# mclon_nano_0_1.net
KiCad netlist of a schematic drawn in EAGLE
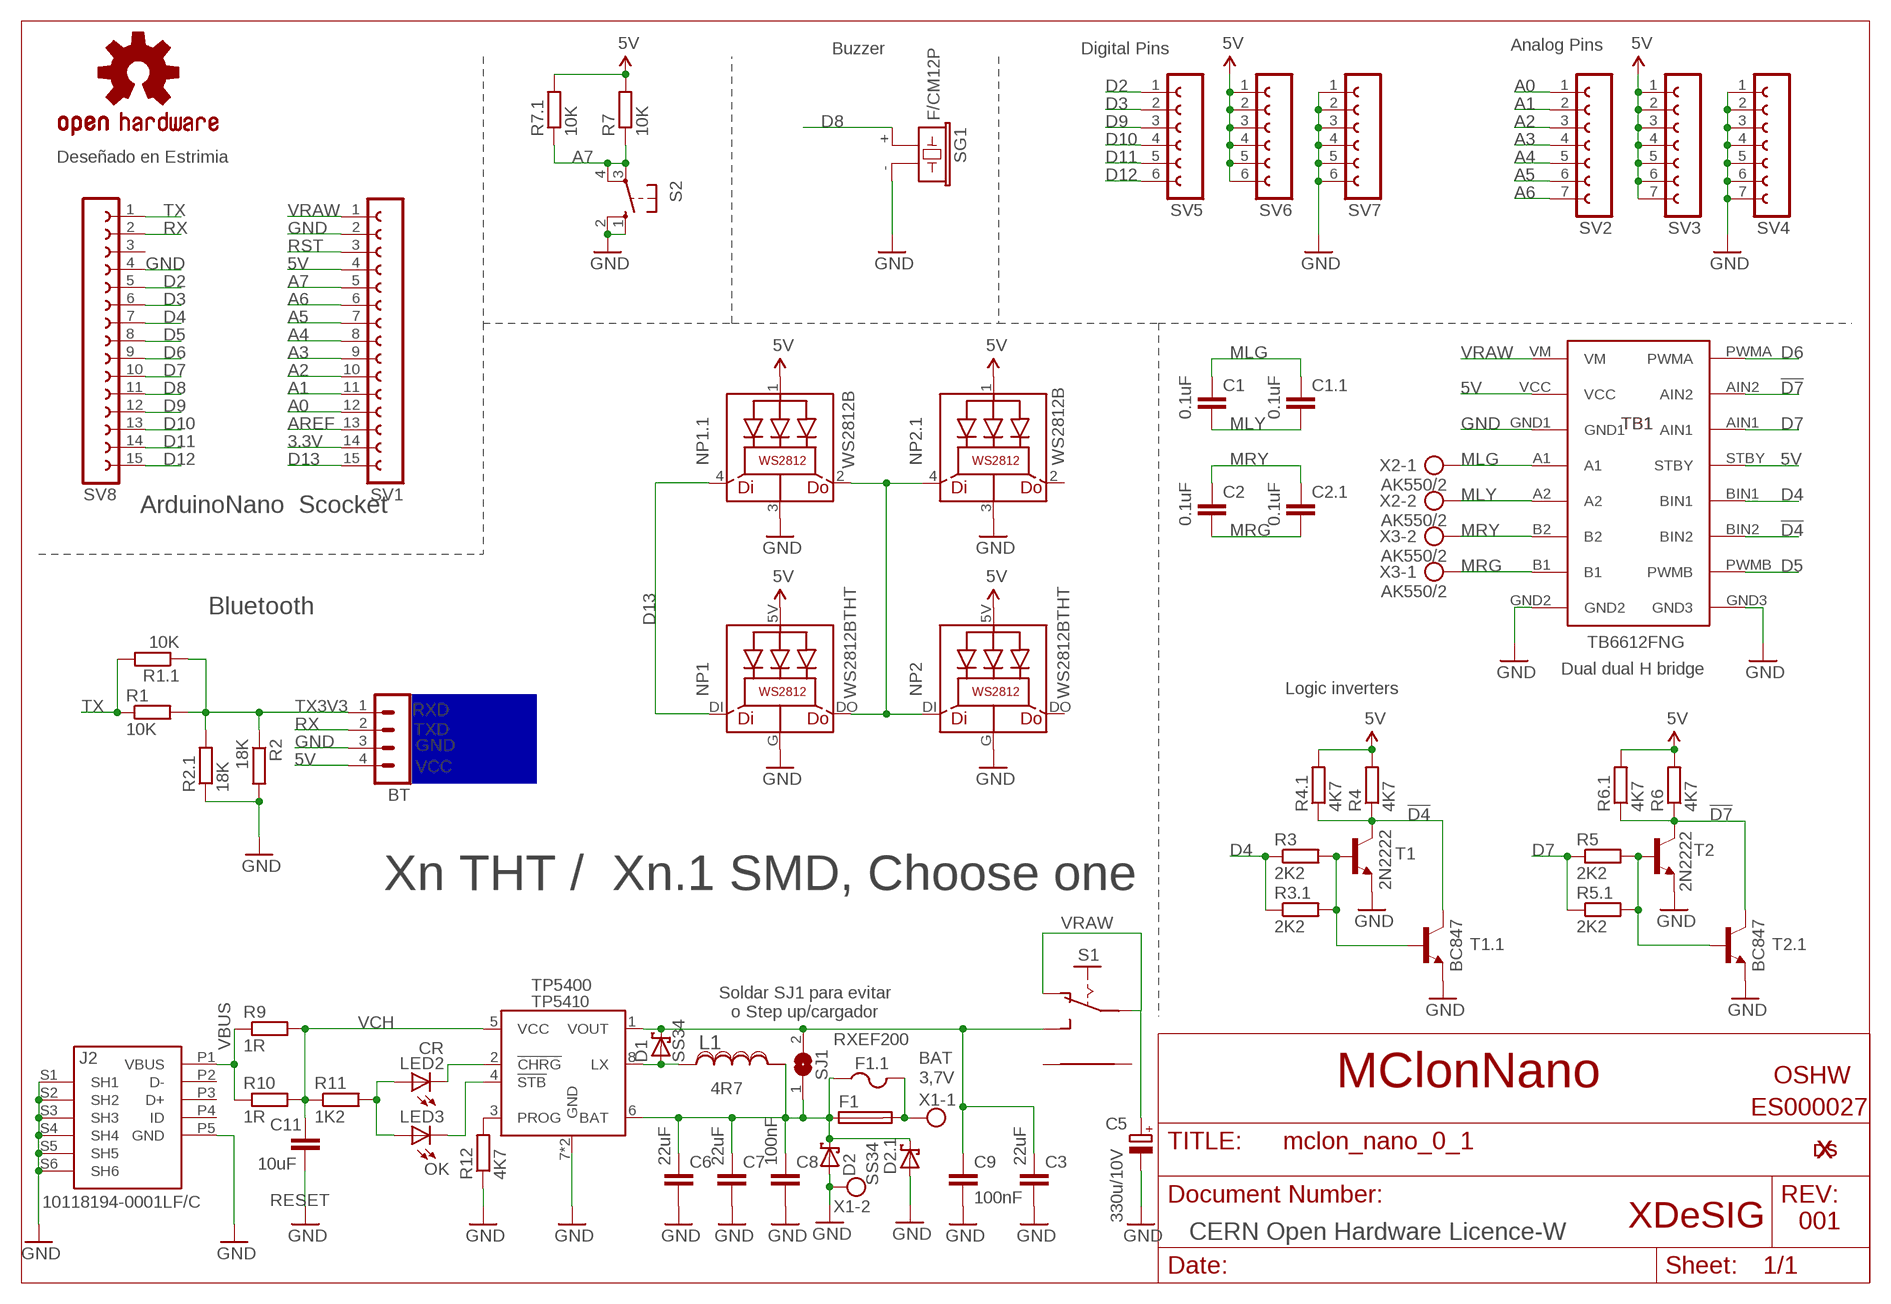
[diagram p0: schematic, sheet 1]

(export (version "E")
  (design (tool "Eeschema 10.0.6"))
  (components
    (comp (ref "BT")
      (value "MA04-1")
      (footprint "eagle-import:MA04-1")
      (libsource (lib "eagle-import") (part "MA04-1"))
    )
    (comp (ref "C1")
      (value "0.1uF")
      (footprint "eagle-import:C050-024X044")
      (libsource (lib "eagle-import") (part "C-EU050-024X044"))
    )
    (comp (ref "C1.1")
      (value "0.1uF")
      (footprint "eagle-import:C1206")
      (libsource (lib "eagle-import") (part "C-EUC1206"))
    )
    (comp (ref "C2")
      (value "0.1uF")
      (footprint "eagle-import:C050-024X044")
      (libsource (lib "eagle-import") (part "C-EU050-024X044"))
    )
    (comp (ref "C2.1")
      (value "0.1uF")
      (footprint "eagle-import:C1206")
      (libsource (lib "eagle-import") (part "C-EUC1206"))
    )
    (comp (ref "C3")
      (value "22uF")
      (footprint "eagle-import:C1206")
      (libsource (lib "eagle-import") (part "C-EUC1206"))
    )
    (comp (ref "C5")
      (value "330u/10V")
      (footprint "eagle-import:E2,5-6")
      (libsource (lib "eagle-import") (part "CPOL-EUE2.5-6"))
    )
    (comp (ref "C6")
      (value "22uF")
      (footprint "eagle-import:C1206")
      (libsource (lib "eagle-import") (part "C-EUC1206"))
    )
    (comp (ref "C7")
      (value "22uF")
      (footprint "eagle-import:C1206")
      (libsource (lib "eagle-import") (part "C-EUC1206"))
    )
    (comp (ref "C8")
      (value "100nF")
      (footprint "eagle-import:C1206")
      (libsource (lib "eagle-import") (part "C-EUC1206"))
    )
    (comp (ref "C9")
      (value "100nF")
      (footprint "eagle-import:C1206")
      (libsource (lib "eagle-import") (part "C-EUC1206"))
    )
    (comp (ref "C11")
      (value "10uF")
      (footprint "eagle-import:C1206")
      (libsource (lib "eagle-import") (part "C-EUC1206"))
    )
    (comp (ref "D1")
      (value "SS34")
      (footprint "eagle-import:DIODE_SMA")
      (libsource (lib "eagle-import") (part "DIODE_SCHOTTKY-DIODESMA"))
    )
    (comp (ref "D2")
      (value "SS34")
      (footprint "eagle-import:DIODE_SMA")
      (libsource (lib "eagle-import") (part "DIODE_SCHOTTKY-DIODESMA"))
    )
    (comp (ref "D2.1")
      (value "SCHOTTKY-DIODEDO35-7")
      (footprint "eagle-import:DO35-7")
      (libsource (lib "eagle-import") (part "SCHOTTKY-DIODEDO35-7"))
    )
    (comp (ref "F1")
      (value "RXEF200")
      (footprint "eagle-import:TE5")
      (libsource (lib "eagle-import") (part "FUSETE5"))
    )
    (comp (ref "F1.1")
      (value "MF-NSMF200")
      (footprint "eagle-import:1812")
      (libsource (lib "eagle-import") (part "PTCFUSE-1812"))
    )
    (comp (ref "J2")
      (value "10118194-0001LF/C")
      (footprint "eagle-import:SMARTPRJ_CON2_USB_MICRO_B_AT")
      (libsource (lib "eagle-import") (part "SMARTPRJ_MYCON2_USB-MINI-B"))
    )
    (comp (ref "L1")
      (value "4R7")
      (footprint "eagle-import:SRN6045")
      (fields (field (name "MF") "Bourns") (field (name "MP") "SRN6045-330M"))
      (libsource (lib "eagle-import") (part "SRN6045-330M6045"))
    )
    (comp (ref "LED2")
      (value "CR")
      (footprint "eagle-import:CHIPLED_0805")
      (libsource (lib "eagle-import") (part "LEDCHIPLED_0805"))
    )
    (comp (ref "LED3")
      (value "OK")
      (footprint "eagle-import:CHIPLED_0805")
      (libsource (lib "eagle-import") (part "LEDCHIPLED_0805"))
    )
    (comp (ref "LOGO4")
      (value "OSHW-LOGOS")
      (footprint "eagle-import:OSHW-LOGO-S")
      (libsource (lib "eagle-import") (part "OSHW-LOGOS"))
    )
    (comp (ref "NP1")
      (value "WS2812BTHT")
      (footprint "eagle-import:NEOPIXEL5MM")
      (libsource (lib "eagle-import") (part "WS2812BTHT"))
    )
    (comp (ref "NP1.1")
      (value "WS2812B")
      (footprint "eagle-import:5050-4")
      (libsource (lib "eagle-import") (part "WS2812B"))
    )
    (comp (ref "NP2")
      (value "WS2812BTHT")
      (footprint "eagle-import:NEOPIXEL5MM")
      (libsource (lib "eagle-import") (part "WS2812BTHT"))
    )
    (comp (ref "NP2.1")
      (value "WS2812B")
      (footprint "eagle-import:5050-4")
      (libsource (lib "eagle-import") (part "WS2812B"))
    )
    (comp (ref "R1")
      (value "10K")
      (footprint "eagle-import:0204_7")
      (libsource (lib "eagle-import") (part "R-EU_0204/7"))
    )
    (comp (ref "R1.1")
      (value "10K")
      (footprint "eagle-import:R1206")
      (libsource (lib "eagle-import") (part "R-EU_R1206"))
    )
    (comp (ref "R2")
      (value "18K")
      (footprint "eagle-import:0204_7")
      (libsource (lib "eagle-import") (part "R-EU_0204/7"))
    )
    (comp (ref "R2.1")
      (value "18K")
      (footprint "eagle-import:R1206")
      (libsource (lib "eagle-import") (part "R-EU_R1206"))
    )
    (comp (ref "R3")
      (value "2K2")
      (footprint "eagle-import:0204_7")
      (libsource (lib "eagle-import") (part "R-EU_0204/7"))
    )
    (comp (ref "R3.1")
      (value "2K2")
      (footprint "eagle-import:R1206")
      (libsource (lib "eagle-import") (part "R-EU_R1206"))
    )
    (comp (ref "R4")
      (value "4K7")
      (footprint "eagle-import:0204_7")
      (libsource (lib "eagle-import") (part "R-EU_0204/7"))
    )
    (comp (ref "R4.1")
      (value "4K7")
      (footprint "eagle-import:R1206")
      (libsource (lib "eagle-import") (part "R-EU_R1206"))
    )
    (comp (ref "R5")
      (value "2K2")
      (footprint "eagle-import:0204_7")
      (libsource (lib "eagle-import") (part "R-EU_0204/7"))
    )
    (comp (ref "R5.1")
      (value "2K2")
      (footprint "eagle-import:R1206")
      (libsource (lib "eagle-import") (part "R-EU_R1206"))
    )
    (comp (ref "R6")
      (value "4K7")
      (footprint "eagle-import:0204_7")
      (libsource (lib "eagle-import") (part "R-EU_0204/7"))
    )
    (comp (ref "R6.1")
      (value "4K7")
      (footprint "eagle-import:R1206")
      (libsource (lib "eagle-import") (part "R-EU_R1206"))
    )
    (comp (ref "R7")
      (value "10K")
      (footprint "eagle-import:0204_7")
      (libsource (lib "eagle-import") (part "R-EU_0204/7"))
    )
    (comp (ref "R7.1")
      (value "10K")
      (footprint "eagle-import:R1206")
      (libsource (lib "eagle-import") (part "R-EU_R1206"))
    )
    (comp (ref "R9")
      (value "1R")
      (footprint "eagle-import:M1206")
      (libsource (lib "eagle-import") (part "R-EU_M1206"))
    )
    (comp (ref "R10")
      (value "1R")
      (footprint "eagle-import:M1206")
      (libsource (lib "eagle-import") (part "R-EU_M1206"))
    )
    (comp (ref "R11")
      (value "1K2")
      (footprint "eagle-import:R1206")
      (libsource (lib "eagle-import") (part "R-EU_R1206"))
    )
    (comp (ref "R12")
      (value "4K7")
      (footprint "eagle-import:R1206")
      (libsource (lib "eagle-import") (part "R-EU_R1206"))
    )
    (comp (ref "S1")
      (value "ESCORNA_SK12F14D")
      (footprint "eagle-import:ESCORNA_SK-12D07")
      (libsource (lib "eagle-import") (part "ESCORNA_SK12F14D"))
    )
    (comp (ref "S2")
      (value "10-XX")
      (footprint "eagle-import:B3F-10XX")
      (fields (field (name "MPN") "B3F-1000"))
      (libsource (lib "eagle-import") (part "10-XX"))
    )
    (comp (ref "SG1")
      (value "F/CM12P")
      (footprint "eagle-import:F_CM12P")
      (libsource (lib "eagle-import") (part "F/CM12P"))
    )
    (comp (ref "SJ1")
      (value "JUMPER_SJW")
      (footprint "eagle-import:JUMPER_SJW")
      (libsource (lib "eagle-import") (part "JUMPER_SJW"))
    )
    (comp (ref "SV1")
      (value "CON-LSTA_FE15-1")
      (footprint "eagle-import:CON-LSTA_FE15")
      (libsource (lib "eagle-import") (part "CON-LSTA_FE15-1"))
    )
    (comp (ref "SV2")
      (value "FE07-1")
      (footprint "eagle-import:FE07")
      (libsource (lib "eagle-import") (part "FE07-1"))
    )
    (comp (ref "SV3")
      (value "FE07-1")
      (footprint "eagle-import:FE07")
      (libsource (lib "eagle-import") (part "FE07-1"))
    )
    (comp (ref "SV4")
      (value "FE07-1")
      (footprint "eagle-import:FE07")
      (libsource (lib "eagle-import") (part "FE07-1"))
    )
    (comp (ref "SV5")
      (value "FE06-1")
      (footprint "eagle-import:FE06")
      (libsource (lib "eagle-import") (part "FE06-1"))
    )
    (comp (ref "SV6")
      (value "FE06-1")
      (footprint "eagle-import:FE06")
      (libsource (lib "eagle-import") (part "FE06-1"))
    )
    (comp (ref "SV7")
      (value "FE06-1")
      (footprint "eagle-import:FE06")
      (libsource (lib "eagle-import") (part "FE06-1"))
    )
    (comp (ref "SV8")
      (value "CON-LSTA_FE15-1")
      (footprint "eagle-import:CON-LSTA_FE15")
      (libsource (lib "eagle-import") (part "CON-LSTA_FE15-1"))
    )
    (comp (ref "T1")
      (value "2N2222")
      (footprint "eagle-import:TO92-EBC-OVAL")
      (libsource (lib "eagle-import") (part "2N2222"))
    )
    (comp (ref "T1.1")
      (value "BC847")
      (footprint "eagle-import:SOT23")
      (libsource (lib "eagle-import") (part "BC847"))
    )
    (comp (ref "T2")
      (value "2N2222")
      (footprint "eagle-import:TO92-EBC-OVAL")
      (libsource (lib "eagle-import") (part "2N2222"))
    )
    (comp (ref "T2.1")
      (value "BC847")
      (footprint "eagle-import:SOT23")
      (libsource (lib "eagle-import") (part "BC847"))
    )
    (comp (ref "TB1")
      (value "TB6612FNG")
      (footprint "eagle-import:TB6612FNG")
      (libsource (lib "eagle-import") (part "TB6612FNG"))
    )
    (comp (ref "U$7")
      (value "OSHW")
      (footprint "eagle-import:OSHW")
      (libsource (lib "eagle-import") (part "OSHW"))
    )
    (comp (ref "U$8")
      (value "XDESIG5MM")
      (footprint "eagle-import:XDESIG_CU")
      (libsource (lib "eagle-import") (part "XDESIG5MM"))
    )
    (comp (ref "U$18")
      (value "XDESIG21")
      (footprint "eagle-import:XDESIG")
      (libsource (lib "eagle-import") (part "XDESIG21"))
    )
    (comp (ref "U$19")
      (value "XDESIG5MM")
      (footprint "eagle-import:XDESIG_CU")
      (libsource (lib "eagle-import") (part "XDESIG5MM"))
    )
    (comp (ref "U1")
      (value "TP5400")
      (footprint "eagle-import:ESOP8")
      (libsource (lib "eagle-import") (part "TP5400"))
    )
    (comp (ref "X1")
      (value "AK550/2")
      (footprint "eagle-import:AK550_2")
      (libsource (lib "eagle-import") (part "AK550/2"))
    )
    (comp (ref "X2")
      (value "AK550/2")
      (footprint "eagle-import:AK550_2")
      (libsource (lib "eagle-import") (part "AK550/2"))
    )
    (comp (ref "X3")
      (value "AK550/2")
      (footprint "eagle-import:AK550_2")
      (libsource (lib "eagle-import") (part "AK550/2"))
    )
  )
  (nets
    (net (code "1") (name "/3.3V") (class "Default")
      (node (ref "SV1") (pin "14") (pinfunction "14_14") (pintype "passive"))
    )
    (net (code "2") (name "/A0") (class "Default")
      (node (ref "SV1") (pin "12") (pinfunction "12_12") (pintype "passive"))
      (node (ref "SV2") (pin "1") (pinfunction "1_1") (pintype "passive"))
    )
    (net (code "3") (name "/A1") (class "Default")
      (node (ref "SV1") (pin "11") (pinfunction "11_11") (pintype "passive"))
      (node (ref "SV2") (pin "2") (pinfunction "2_2") (pintype "passive"))
    )
    (net (code "4") (name "/A2") (class "Default")
      (node (ref "SV1") (pin "10") (pinfunction "10_10") (pintype "passive"))
      (node (ref "SV2") (pin "3") (pinfunction "3_3") (pintype "passive"))
    )
    (net (code "5") (name "/A3") (class "Default")
      (node (ref "SV1") (pin "9") (pinfunction "9_9") (pintype "passive"))
      (node (ref "SV2") (pin "4") (pinfunction "4_4") (pintype "passive"))
    )
    (net (code "6") (name "/A4") (class "Default")
      (node (ref "SV1") (pin "8") (pinfunction "8_8") (pintype "passive"))
      (node (ref "SV2") (pin "5") (pinfunction "5_5") (pintype "passive"))
    )
    (net (code "7") (name "/A5") (class "Default")
      (node (ref "SV1") (pin "7") (pinfunction "7_7") (pintype "passive"))
      (node (ref "SV2") (pin "6") (pinfunction "6_6") (pintype "passive"))
    )
    (net (code "8") (name "/A6") (class "Default")
      (node (ref "SV1") (pin "6") (pinfunction "6_6") (pintype "passive"))
      (node (ref "SV2") (pin "7") (pinfunction "7_7") (pintype "passive"))
    )
    (net (code "9") (name "/A7") (class "Default")
      (node (ref "R7") (pin "1") (pinfunction "1_1") (pintype "passive"))
      (node (ref "R7.1") (pin "1") (pinfunction "1_1") (pintype "passive"))
      (node (ref "S2") (pin "3") (pinfunction "P_3") (pintype "passive"))
      (node (ref "S2") (pin "4") (pinfunction "P1_4") (pintype "passive"))
      (node (ref "SV1") (pin "5") (pinfunction "5_5") (pintype "passive"))
    )
    (net (code "10") (name "/AREF") (class "Default")
      (node (ref "SV1") (pin "13") (pinfunction "13_13") (pintype "passive"))
    )
    (net (code "11") (name "/BAT") (class "Default")
      (node (ref "C6") (pin "1") (pinfunction "1_1") (pintype "passive"))
      (node (ref "C7") (pin "1") (pinfunction "1_1") (pintype "passive"))
      (node (ref "C8") (pin "1") (pinfunction "1_1") (pintype "passive"))
      (node (ref "D2") (pin "C") (pinfunction "C_C") (pintype "passive"))
      (node (ref "D2.1") (pin "C") (pinfunction "C_C") (pintype "passive"))
      (node (ref "F1") (pin "1") (pinfunction "1_1") (pintype "passive"))
      (node (ref "F1.1") (pin "1") (pinfunction "1_1") (pintype "passive"))
      (node (ref "L1") (pin "1") (pinfunction "1_1") (pintype "passive"))
      (node (ref "SJ1") (pin "1") (pinfunction "1_1") (pintype "passive"))
      (node (ref "U1") (pin "6") (pinfunction "BAT_6") (pintype "bidirectional"))
    )
    (net (code "12") (name "/D2") (class "Default")
      (node (ref "SV5") (pin "1") (pinfunction "1_1") (pintype "passive"))
      (node (ref "SV8") (pin "5") (pinfunction "5_5") (pintype "passive"))
    )
    (net (code "13") (name "/D3") (class "Default")
      (node (ref "SV5") (pin "2") (pinfunction "2_2") (pintype "passive"))
      (node (ref "SV8") (pin "6") (pinfunction "6_6") (pintype "passive"))
    )
    (net (code "14") (name "/D4") (class "Default")
      (node (ref "R3") (pin "1") (pinfunction "1_1") (pintype "passive"))
      (node (ref "R3.1") (pin "1") (pinfunction "1_1") (pintype "passive"))
      (node (ref "SV8") (pin "7") (pinfunction "7_7") (pintype "passive"))
      (node (ref "TB1") (pin "BIN1") (pinfunction "BIN1_BIN1") (pintype "bidirectional"))
    )
    (net (code "15") (name "/D5") (class "Default")
      (node (ref "SV8") (pin "8") (pinfunction "8_8") (pintype "passive"))
      (node (ref "TB1") (pin "PWMB") (pinfunction "PWMB_PWMB") (pintype "bidirectional"))
    )
    (net (code "16") (name "/D6") (class "Default")
      (node (ref "SV8") (pin "9") (pinfunction "9_9") (pintype "passive"))
      (node (ref "TB1") (pin "PWMA") (pinfunction "PWMA_PWMA") (pintype "bidirectional"))
    )
    (net (code "17") (name "/D7") (class "Default")
      (node (ref "R5") (pin "1") (pinfunction "1_1") (pintype "passive"))
      (node (ref "R5.1") (pin "1") (pinfunction "1_1") (pintype "passive"))
      (node (ref "SV8") (pin "10") (pinfunction "10_10") (pintype "passive"))
      (node (ref "TB1") (pin "AIN1") (pinfunction "AIN1_AIN1") (pintype "bidirectional"))
    )
    (net (code "18") (name "/D8") (class "Default")
      (node (ref "SG1") (pin "+") (pinfunction "1_+") (pintype "passive"))
      (node (ref "SV8") (pin "11") (pinfunction "11_11") (pintype "passive"))
    )
    (net (code "19") (name "/D9") (class "Default")
      (node (ref "SV5") (pin "3") (pinfunction "3_3") (pintype "passive"))
      (node (ref "SV8") (pin "12") (pinfunction "12_12") (pintype "passive"))
    )
    (net (code "20") (name "/D10") (class "Default")
      (node (ref "SV5") (pin "4") (pinfunction "4_4") (pintype "passive"))
      (node (ref "SV8") (pin "13") (pinfunction "13_13") (pintype "passive"))
    )
    (net (code "21") (name "/D11") (class "Default")
      (node (ref "SV5") (pin "5") (pinfunction "5_5") (pintype "passive"))
      (node (ref "SV8") (pin "14") (pinfunction "14_14") (pintype "passive"))
    )
    (net (code "22") (name "/D12") (class "Default")
      (node (ref "SV5") (pin "6") (pinfunction "6_6") (pintype "passive"))
      (node (ref "SV8") (pin "15") (pinfunction "15_15") (pintype "passive"))
    )
    (net (code "23") (name "/D13") (class "Default")
      (node (ref "NP1") (pin "DI") (pinfunction "DI_DI") (pintype "input"))
      (node (ref "NP1.1") (pin "4") (pinfunction "DI_4") (pintype "input"))
      (node (ref "SV1") (pin "15") (pinfunction "15_15") (pintype "passive"))
    )
    (net (code "24") (name "/MLG") (class "Default")
      (node (ref "C1") (pin "1") (pinfunction "1_1") (pintype "passive"))
      (node (ref "C1.1") (pin "1") (pinfunction "1_1") (pintype "passive"))
      (node (ref "TB1") (pin "A1") (pinfunction "A1_A1") (pintype "bidirectional"))
      (node (ref "X2") (pin "1") (pinfunction "KL_1") (pintype "passive"))
    )
    (net (code "25") (name "/MLY") (class "Default")
      (node (ref "C1") (pin "2") (pinfunction "2_2") (pintype "passive"))
      (node (ref "C1.1") (pin "2") (pinfunction "2_2") (pintype "passive"))
      (node (ref "TB1") (pin "A2") (pinfunction "A2_A2") (pintype "bidirectional"))
      (node (ref "X2") (pin "2") (pinfunction "KL_2") (pintype "passive"))
    )
    (net (code "26") (name "/MRG") (class "Default")
      (node (ref "C2") (pin "2") (pinfunction "2_2") (pintype "passive"))
      (node (ref "C2.1") (pin "2") (pinfunction "2_2") (pintype "passive"))
      (node (ref "TB1") (pin "B1") (pinfunction "B1_B1") (pintype "bidirectional"))
      (node (ref "X3") (pin "1") (pinfunction "KL_1") (pintype "passive"))
    )
    (net (code "27") (name "/MRY") (class "Default")
      (node (ref "C2") (pin "1") (pinfunction "1_1") (pintype "passive"))
      (node (ref "C2.1") (pin "1") (pinfunction "1_1") (pintype "passive"))
      (node (ref "TB1") (pin "B2") (pinfunction "B2_B2") (pintype "bidirectional"))
      (node (ref "X3") (pin "2") (pinfunction "KL_2") (pintype "passive"))
    )
    (net (code "29") (name "/RST") (class "Default")
      (node (ref "SV1") (pin "3") (pinfunction "3_3") (pintype "passive"))
    )
    (net (code "30") (name "/RX") (class "Default")
      (node (ref "BT") (pin "2") (pinfunction "2_2") (pintype "passive"))
      (node (ref "SV8") (pin "2") (pinfunction "2_2") (pintype "passive"))
    )
    (net (code "31") (name "/TX") (class "Default")
      (node (ref "R1") (pin "1") (pinfunction "1_1") (pintype "passive"))
      (node (ref "R1.1") (pin "2") (pinfunction "2_2") (pintype "passive"))
      (node (ref "SV8") (pin "1") (pinfunction "1_1") (pintype "passive"))
    )
    (net (code "32") (name "/TX3V3") (class "Default")
      (node (ref "BT") (pin "1") (pinfunction "1_1") (pintype "passive"))
      (node (ref "R1") (pin "2") (pinfunction "2_2") (pintype "passive"))
      (node (ref "R1.1") (pin "1") (pinfunction "1_1") (pintype "passive"))
      (node (ref "R2") (pin "1") (pinfunction "1_1") (pintype "passive"))
      (node (ref "R2.1") (pin "2") (pinfunction "2_2") (pintype "passive"))
    )
    (net (code "33") (name "/VBUS") (class "Default")
      (node (ref "J2") (pin "P1") (pinfunction "VBUS_P1") (pintype "power_in"))
      (node (ref "R10") (pin "1") (pinfunction "1_1") (pintype "passive"))
      (node (ref "R9") (pin "1") (pinfunction "1_1") (pintype "passive"))
    )
    (net (code "34") (name "/VCH") (class "Default")
      (node (ref "C11") (pin "1") (pinfunction "1_1") (pintype "passive"))
      (node (ref "R10") (pin "2") (pinfunction "2_2") (pintype "passive"))
      (node (ref "R11") (pin "1") (pinfunction "1_1") (pintype "passive"))
      (node (ref "R9") (pin "2") (pinfunction "2_2") (pintype "passive"))
      (node (ref "U1") (pin "5") (pinfunction "VCC_5") (pintype "power_in"))
    )
    (net (code "35") (name "/VRAW") (class "Default")
      (node (ref "C5") (pin "+") (pinfunction "+_+") (pintype "passive"))
      (node (ref "S1") (pin "P$1") (pinfunction "P_P$1") (pintype "passive"))
      (node (ref "S1") (pin "P$2") (pinfunction "O_P$2") (pintype "passive"))
      (node (ref "SV1") (pin "1") (pinfunction "1_1") (pintype "passive"))
      (node (ref "TB1") (pin "VM") (pinfunction "VM_VM") (pintype "bidirectional"))
    )
    (net (code "36") (name "/~{D4}") (class "Default")
      (node (ref "R4") (pin "1") (pinfunction "1_1") (pintype "passive"))
      (node (ref "R4.1") (pin "1") (pinfunction "1_1") (pintype "passive"))
      (node (ref "T1") (pin "C") (pinfunction "C_C") (pintype "passive"))
      (node (ref "T1.1") (pin "3") (pinfunction "C_3") (pintype "passive"))
      (node (ref "TB1") (pin "BIN2") (pinfunction "BIN2_BIN2") (pintype "bidirectional"))
    )
    (net (code "37") (name "/~{D7}") (class "Default")
      (node (ref "R6") (pin "1") (pinfunction "1_1") (pintype "passive"))
      (node (ref "R6.1") (pin "1") (pinfunction "1_1") (pintype "passive"))
      (node (ref "T2") (pin "C") (pinfunction "C_C") (pintype "passive"))
      (node (ref "T2.1") (pin "3") (pinfunction "C_3") (pintype "passive"))
      (node (ref "TB1") (pin "AIN2") (pinfunction "AIN2_AIN2") (pintype "bidirectional"))
    )
    (net (code "38") (name "5V") (class "Default")
      (node (ref "BT") (pin "4") (pinfunction "4_4") (pintype "passive"))
      (node (ref "NP1") (pin "5V") (pinfunction "LEDVDD_5V") (pintype "power_in"))
      (node (ref "NP1.1") (pin "1") (pinfunction "LEDVDD_1") (pintype "power_in"))
      (node (ref "NP2") (pin "5V") (pinfunction "LEDVDD_5V") (pintype "power_in"))
      (node (ref "NP2.1") (pin "1") (pinfunction "LEDVDD_1") (pintype "power_in"))
      (node (ref "R4") (pin "2") (pinfunction "2_2") (pintype "passive"))
      (node (ref "R4.1") (pin "2") (pinfunction "2_2") (pintype "passive"))
      (node (ref "R6") (pin "2") (pinfunction "2_2") (pintype "passive"))
      (node (ref "R6.1") (pin "2") (pinfunction "2_2") (pintype "passive"))
      (node (ref "R7") (pin "2") (pinfunction "2_2") (pintype "passive"))
      (node (ref "R7.1") (pin "2") (pinfunction "2_2") (pintype "passive"))
      (node (ref "SV1") (pin "4") (pinfunction "4_4") (pintype "passive"))
      (node (ref "SV3") (pin "1") (pinfunction "1_1") (pintype "passive"))
      (node (ref "SV3") (pin "2") (pinfunction "2_2") (pintype "passive"))
      (node (ref "SV3") (pin "3") (pinfunction "3_3") (pintype "passive"))
      (node (ref "SV3") (pin "4") (pinfunction "4_4") (pintype "passive"))
      (node (ref "SV3") (pin "5") (pinfunction "5_5") (pintype "passive"))
      (node (ref "SV3") (pin "6") (pinfunction "6_6") (pintype "passive"))
      (node (ref "SV3") (pin "7") (pinfunction "7_7") (pintype "passive"))
      (node (ref "SV6") (pin "1") (pinfunction "1_1") (pintype "passive"))
      (node (ref "SV6") (pin "2") (pinfunction "2_2") (pintype "passive"))
      (node (ref "SV6") (pin "3") (pinfunction "3_3") (pintype "passive"))
      (node (ref "SV6") (pin "4") (pinfunction "4_4") (pintype "passive"))
      (node (ref "SV6") (pin "5") (pinfunction "5_5") (pintype "passive"))
      (node (ref "SV6") (pin "6") (pinfunction "6_6") (pintype "passive"))
      (node (ref "TB1") (pin "STBY") (pinfunction "STBY_STBY") (pintype "bidirectional"))
      (node (ref "TB1") (pin "VCC") (pinfunction "VCC_VCC") (pintype "bidirectional"))
    )
    (net (code "39") (name "GND") (class "Default")
      (node (ref "BT") (pin "3") (pinfunction "3_3") (pintype "passive"))
      (node (ref "C11") (pin "2") (pinfunction "2_2") (pintype "passive"))
      (node (ref "C3") (pin "2") (pinfunction "2_2") (pintype "passive"))
      (node (ref "C5") (pin "-") (pinfunction "-_-") (pintype "passive"))
      (node (ref "C6") (pin "2") (pinfunction "2_2") (pintype "passive"))
      (node (ref "C7") (pin "2") (pinfunction "2_2") (pintype "passive"))
      (node (ref "C8") (pin "2") (pinfunction "2_2") (pintype "passive"))
      (node (ref "C9") (pin "2") (pinfunction "2_2") (pintype "passive"))
      (node (ref "D2") (pin "A") (pinfunction "A_A") (pintype "passive"))
      (node (ref "D2.1") (pin "A") (pinfunction "A_A") (pintype "passive"))
      (node (ref "J2") (pin "P5") (pinfunction "GND_P5") (pintype "passive"))
      (node (ref "J2") (pin "S1") (pinfunction "SH1_S1") (pintype "passive"))
      (node (ref "J2") (pin "S2") (pinfunction "SH2_S2") (pintype "passive"))
      (node (ref "J2") (pin "S3") (pinfunction "SH3_S3") (pintype "passive"))
      (node (ref "J2") (pin "S4") (pinfunction "SH4_S4") (pintype "passive"))
      (node (ref "J2") (pin "S5") (pinfunction "SH5_S5") (pintype "passive"))
      (node (ref "J2") (pin "S6") (pinfunction "SH6_S6") (pintype "passive"))
      (node (ref "NP1") (pin "G") (pinfunction "GND_G") (pintype "power_in"))
      (node (ref "NP1.1") (pin "3") (pinfunction "GND_3") (pintype "power_in"))
      (node (ref "NP2") (pin "G") (pinfunction "GND_G") (pintype "power_in"))
      (node (ref "NP2.1") (pin "3") (pinfunction "GND_3") (pintype "power_in"))
      (node (ref "R12") (pin "1") (pinfunction "1_1") (pintype "passive"))
      (node (ref "R2") (pin "2") (pinfunction "2_2") (pintype "passive"))
      (node (ref "R2.1") (pin "1") (pinfunction "1_1") (pintype "passive"))
      (node (ref "S2") (pin "1") (pinfunction "S_1") (pintype "passive"))
      (node (ref "S2") (pin "2") (pinfunction "S1_2") (pintype "passive"))
      (node (ref "SG1") (pin "-") (pinfunction "2_-") (pintype "passive"))
      (node (ref "SV1") (pin "2") (pinfunction "2_2") (pintype "passive"))
      (node (ref "SV4") (pin "1") (pinfunction "1_1") (pintype "passive"))
      (node (ref "SV4") (pin "2") (pinfunction "2_2") (pintype "passive"))
      (node (ref "SV4") (pin "3") (pinfunction "3_3") (pintype "passive"))
      (node (ref "SV4") (pin "4") (pinfunction "4_4") (pintype "passive"))
      (node (ref "SV4") (pin "5") (pinfunction "5_5") (pintype "passive"))
      (node (ref "SV4") (pin "6") (pinfunction "6_6") (pintype "passive"))
      (node (ref "SV4") (pin "7") (pinfunction "7_7") (pintype "passive"))
      (node (ref "SV7") (pin "1") (pinfunction "1_1") (pintype "passive"))
      (node (ref "SV7") (pin "2") (pinfunction "2_2") (pintype "passive"))
      (node (ref "SV7") (pin "3") (pinfunction "3_3") (pintype "passive"))
      (node (ref "SV7") (pin "4") (pinfunction "4_4") (pintype "passive"))
      (node (ref "SV7") (pin "5") (pinfunction "5_5") (pintype "passive"))
      (node (ref "SV7") (pin "6") (pinfunction "6_6") (pintype "passive"))
      (node (ref "SV8") (pin "4") (pinfunction "4_4") (pintype "passive"))
      (node (ref "T1") (pin "E") (pinfunction "E_E") (pintype "passive"))
      (node (ref "T1.1") (pin "2") (pinfunction "E_2") (pintype "passive"))
      (node (ref "T2") (pin "E") (pinfunction "E_E") (pintype "passive"))
      (node (ref "T2.1") (pin "2") (pinfunction "E_2") (pintype "passive"))
      (node (ref "TB1") (pin "GND1") (pinfunction "GND1_GND1") (pintype "bidirectional"))
      (node (ref "TB1") (pin "GND2") (pinfunction "GND2_GND2") (pintype "bidirectional"))
      (node (ref "TB1") (pin "GND3") (pinfunction "GND3_GND3") (pintype "bidirectional"))
      (node (ref "U1") (pin "7") (pinfunction "GND_7") (pintype "power_in"))
      (node (ref "U1") (pin "9") (pinfunction "GND_9") (pintype "power_in"))
      (node (ref "X1") (pin "2") (pinfunction "KL_2") (pintype "passive"))
    )
    (net (code "40") (name "Net-(LED2-PadA)") (class "Default")
      (node (ref "LED2") (pin "A") (pinfunction "A_A") (pintype "passive"))
      (node (ref "LED3") (pin "A") (pinfunction "A_A") (pintype "passive"))
      (node (ref "R11") (pin "2") (pinfunction "2_2") (pintype "passive"))
    )
    (net (code "41") (name "Net-(NP1.1-DO)") (class "Default")
      (node (ref "NP1") (pin "DO") (pinfunction "DO_DO") (pintype "output"))
      (node (ref "NP1.1") (pin "2") (pinfunction "DO_2") (pintype "output"))
      (node (ref "NP2") (pin "DI") (pinfunction "DI_DI") (pintype "input"))
      (node (ref "NP2.1") (pin "4") (pinfunction "DI_4") (pintype "input"))
    )
    (net (code "42") (name "Net-(S1-S)") (class "Default")
      (node (ref "C3") (pin "1") (pinfunction "1_1") (pintype "passive"))
      (node (ref "C9") (pin "1") (pinfunction "1_1") (pintype "passive"))
      (node (ref "D1") (pin "C") (pinfunction "C_C") (pintype "passive"))
      (node (ref "S1") (pin "P$3") (pinfunction "S_P$3") (pintype "passive"))
      (node (ref "SJ1") (pin "2") (pinfunction "2_2") (pintype "passive"))
      (node (ref "U1") (pin "1") (pinfunction "VOUT_1") (pintype "power_in"))
    )
    (net (code "43") (name "Net-(T1.1-B)") (class "Default")
      (node (ref "R3") (pin "2") (pinfunction "2_2") (pintype "passive"))
      (node (ref "R3.1") (pin "2") (pinfunction "2_2") (pintype "passive"))
      (node (ref "T1") (pin "B") (pinfunction "B_B") (pintype "passive"))
      (node (ref "T1.1") (pin "1") (pinfunction "B_1") (pintype "passive"))
    )
    (net (code "44") (name "Net-(T2.1-B)") (class "Default")
      (node (ref "R5") (pin "2") (pinfunction "2_2") (pintype "passive"))
      (node (ref "R5.1") (pin "2") (pinfunction "2_2") (pintype "passive"))
      (node (ref "T2") (pin "B") (pinfunction "B_B") (pintype "passive"))
      (node (ref "T2.1") (pin "1") (pinfunction "B_1") (pintype "passive"))
    )
    (net (code "45") (name "Net-(U1-LX)") (class "Default")
      (node (ref "D1") (pin "A") (pinfunction "A_A") (pintype "passive"))
      (node (ref "L1") (pin "2") (pinfunction "2_2") (pintype "passive"))
      (node (ref "U1") (pin "8") (pinfunction "LX_8") (pintype "bidirectional"))
    )
    (net (code "46") (name "Net-(U1-PROG)") (class "Default")
      (node (ref "R12") (pin "2") (pinfunction "2_2") (pintype "passive"))
      (node (ref "U1") (pin "3") (pinfunction "PROG_3") (pintype "bidirectional"))
    )
    (net (code "47") (name "Net-(U1-~{CHRG})") (class "Default")
      (node (ref "LED2") (pin "C") (pinfunction "C_C") (pintype "passive"))
      (node (ref "U1") (pin "2") (pinfunction "~{CHRG}_2") (pintype "bidirectional"))
    )
    (net (code "48") (name "Net-(U1-~{STB})") (class "Default")
      (node (ref "LED3") (pin "C") (pinfunction "C_C") (pintype "passive"))
      (node (ref "U1") (pin "4") (pinfunction "~{STB}_4") (pintype "bidirectional"))
    )
    (net (code "49") (name "Net-(X1A-KL)") (class "Default")
      (node (ref "F1") (pin "2") (pinfunction "2_2") (pintype "passive"))
      (node (ref "F1.1") (pin "2") (pinfunction "2_2") (pintype "passive"))
      (node (ref "X1") (pin "1") (pinfunction "KL_1") (pintype "passive"))
    )
    (net (code "50") (name "unconnected-(J2-D+-PadP3)") (class "Default")
      (node (ref "J2") (pin "P3") (pinfunction "D+_P3") (pintype "bidirectional"))
    )
    (net (code "51") (name "unconnected-(J2-D--PadP2)") (class "Default")
      (node (ref "J2") (pin "P2") (pinfunction "D-_P2") (pintype "bidirectional"))
    )
    (net (code "52") (name "unconnected-(J2-ID-PadP4)") (class "Default")
      (node (ref "J2") (pin "P4") (pinfunction "ID_P4") (pintype "bidirectional"))
    )
    (net (code "53") (name "unconnected-(NP2-PadDO)") (class "Default")
      (node (ref "NP2") (pin "DO") (pinfunction "DO_DO") (pintype "output"))
    )
    (net (code "54") (name "unconnected-(NP2.1-DO-Pad2)") (class "Default")
      (node (ref "NP2.1") (pin "2") (pinfunction "DO_2") (pintype "output"))
    )
    (net (code "55") (name "unconnected-(S1-P$1-PadP$4)") (class "Default")
      (node (ref "S1") (pin "P$4") (pinfunction "P$1_P$4") (pintype "passive"))
    )
    (net (code "56") (name "unconnected-(S1-P$2-PadP$5)") (class "Default")
      (node (ref "S1") (pin "P$5") (pinfunction "P$2_P$5") (pintype "bidirectional"))
    )
    (net (code "57") (name "unconnected-(SV8-Pad3)") (class "Default")
      (node (ref "SV8") (pin "3") (pinfunction "3_3") (pintype "passive"))
    )
  )
)
